# PumpMonitoring.net
KiCad netlist of a schematic drawn in EAGLE
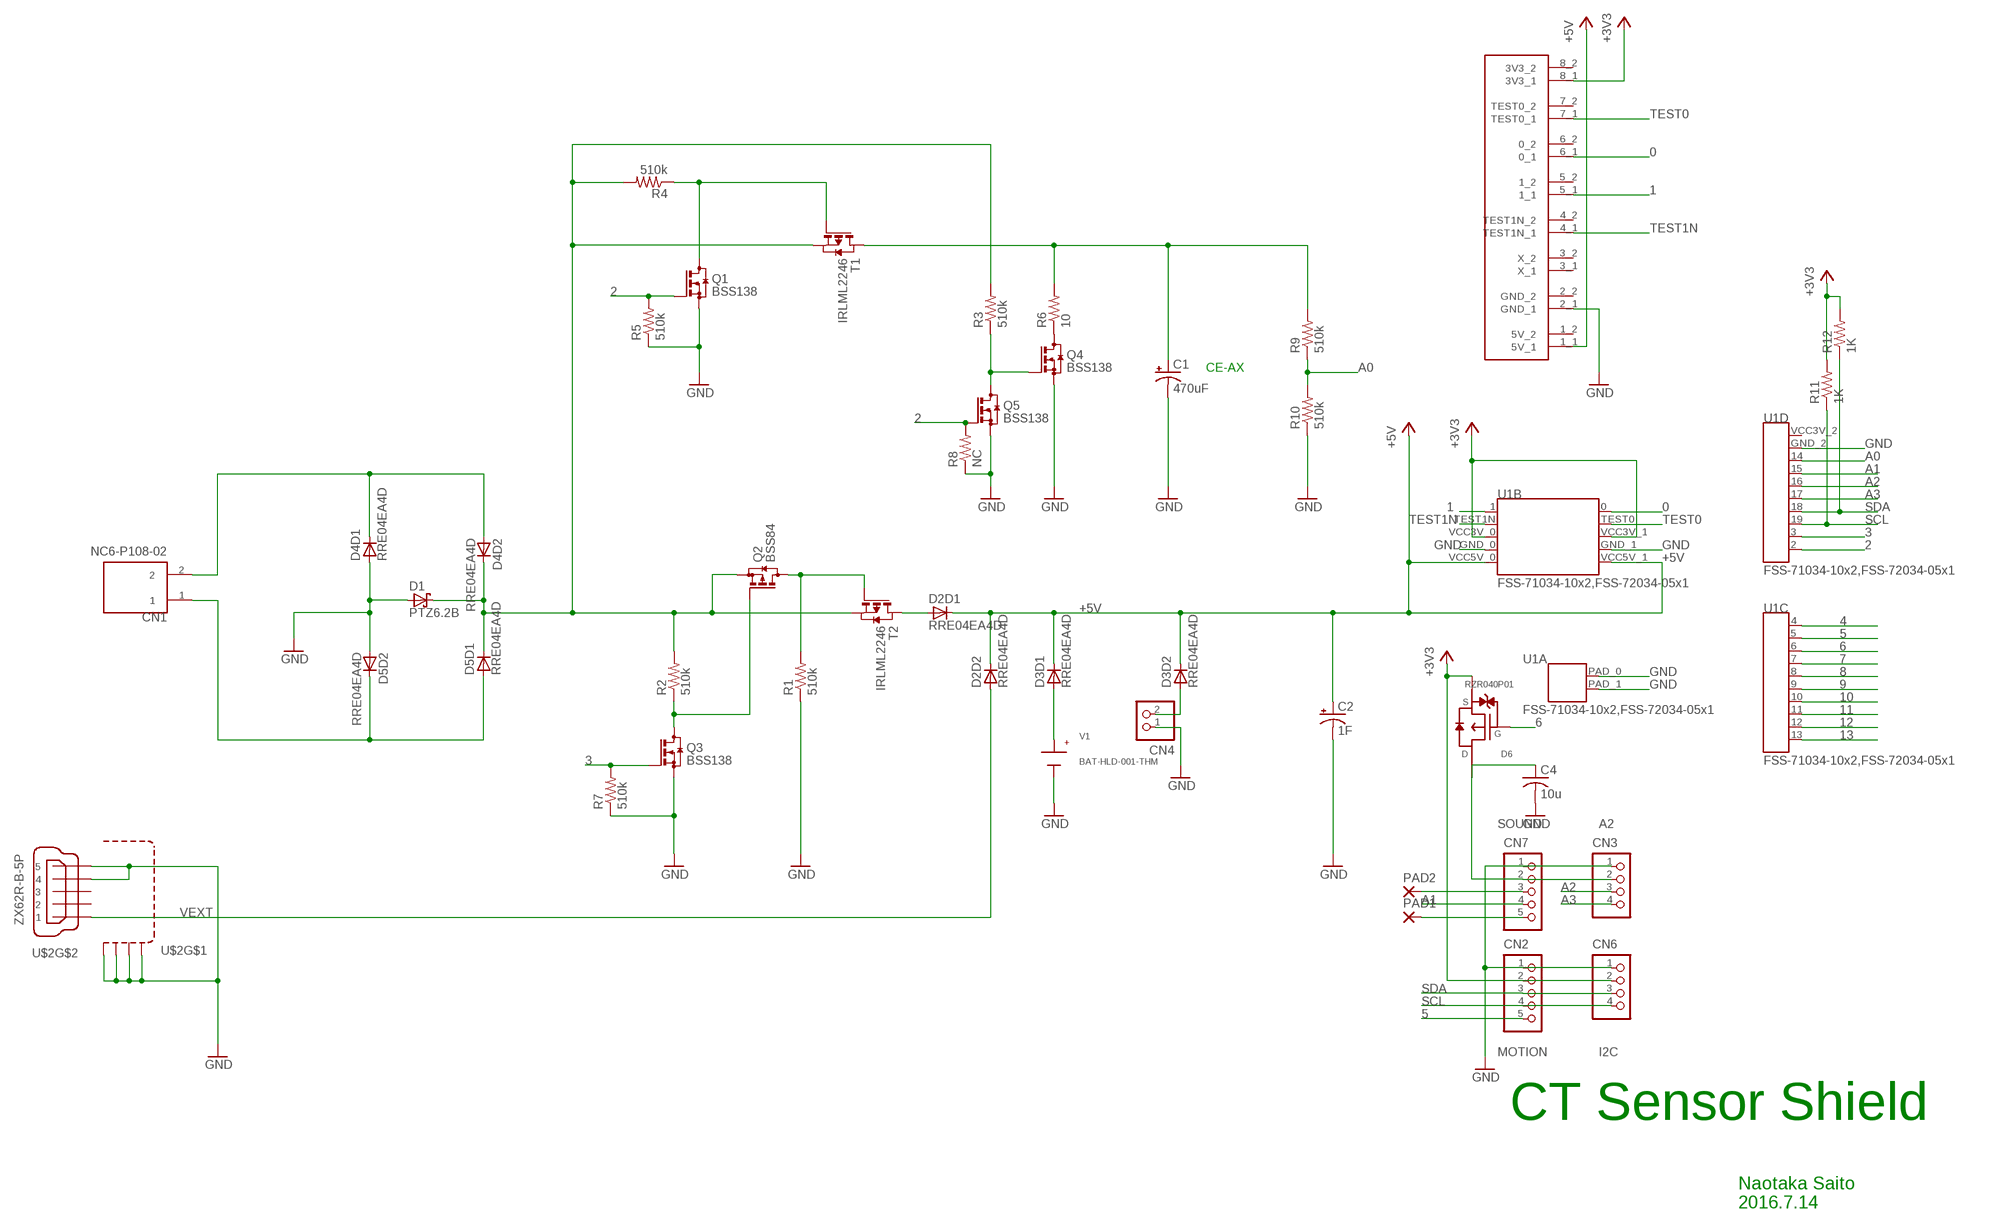
[diagram p0: schematic, sheet 1]

(export (version "E")
  (design (tool "Eeschema 10.0.6"))
  (components
    (comp (ref "C1")
      (value "470uF")
      (footprint "eagle-import:E5-10,5")
      (libsource (lib "eagle-import") (part "CPOL-USE5-10.5"))
    )
    (comp (ref "C2")
      (value "1F")
      (footprint "eagle-import:E5-20")
      (libsource (lib "eagle-import") (part "CPOL-USE5-20"))
    )
    (comp (ref "C4")
      (value "10u")
      (footprint "eagle-import:C1206")
      (libsource (lib "eagle-import") (part "C-USC1206"))
    )
    (comp (ref "CN1")
      (value "NC6-P108-02")
      (footprint "eagle-import:2PIN")
      (libsource (lib "eagle-import") (part "TE-NC6-P108-02"))
    )
    (comp (ref "CN2")
      (value "B5B-PH-K-S")
      (footprint "eagle-import:B5B-PH-K-S")
      (libsource (lib "eagle-import") (part "B5B-PH-K-S"))
    )
    (comp (ref "CN3")
      (value "B4B-PH-K-S")
      (footprint "eagle-import:B4B-PH-K-S")
      (libsource (lib "eagle-import") (part "B4B-PH-K-S"))
    )
    (comp (ref "CN4")
      (value "B2B-PH-K-S")
      (footprint "eagle-import:B2B-PH-K-S")
      (libsource (lib "eagle-import") (part "B2B-PH-K-S"))
    )
    (comp (ref "CN6")
      (value "B4B-PH-K-S")
      (footprint "eagle-import:B4B-PH-K-S")
      (libsource (lib "eagle-import") (part "B4B-PH-K-S"))
    )
    (comp (ref "CN7")
      (value "B5B-PH-K-S")
      (footprint "eagle-import:B5B-PH-K-S")
      (libsource (lib "eagle-import") (part "B5B-PH-K-S"))
    )
    (comp (ref "D1")
      (value "PTZ6.2B")
      (footprint "eagle-import:DO214AC")
      (libsource (lib "eagle-import") (part "PTZXXB"))
    )
    (comp (ref "D2")
      (value "RRE04EA4D")
      (footprint "eagle-import:TSMD5")
      (libsource (lib "eagle-import") (part "RRE04EA4D"))
    )
    (comp (ref "D3")
      (value "RRE04EA4D")
      (footprint "eagle-import:TSMD5")
      (libsource (lib "eagle-import") (part "RRE04EA4D"))
    )
    (comp (ref "D4")
      (value "RRE04EA4D")
      (footprint "eagle-import:TSMD5")
      (libsource (lib "eagle-import") (part "RRE04EA4D"))
    )
    (comp (ref "D5")
      (value "RRE04EA4D")
      (footprint "eagle-import:TSMD5")
      (libsource (lib "eagle-import") (part "RRE04EA4D"))
    )
    (comp (ref "D6")
      (value "RZR040P01")
      (footprint "eagle-import:TSMT3")
      (libsource (lib "eagle-import") (part "RZR040P01"))
    )
    (comp (ref "PAD1")
      (value "1,6/0,9")
      (footprint "eagle-import:1,6_0,9")
      (libsource (lib "eagle-import") (part "1,6/0,9"))
    )
    (comp (ref "PAD2")
      (value "1,6/0,9")
      (footprint "eagle-import:1,6_0,9")
      (libsource (lib "eagle-import") (part "1,6/0,9"))
    )
    (comp (ref "Q1")
      (value "BSS138")
      (footprint "eagle-import:SOT23")
      (libsource (lib "eagle-import") (part "BSS123"))
    )
    (comp (ref "Q2")
      (value "BSS84")
      (footprint "eagle-import:SOT23")
      (libsource (lib "eagle-import") (part "BSS84"))
    )
    (comp (ref "Q3")
      (value "BSS138")
      (footprint "eagle-import:SOT23")
      (libsource (lib "eagle-import") (part "BSS123"))
    )
    (comp (ref "Q4")
      (value "BSS138")
      (footprint "eagle-import:SOT23")
      (libsource (lib "eagle-import") (part "BSS123"))
    )
    (comp (ref "Q5")
      (value "BSS138")
      (footprint "eagle-import:SOT23")
      (libsource (lib "eagle-import") (part "BSS123"))
    )
    (comp (ref "R1")
      (value "510k")
      (footprint "eagle-import:R0603")
      (libsource (lib "eagle-import") (part "R-US_R0603"))
    )
    (comp (ref "R2")
      (value "510k")
      (footprint "eagle-import:R0603")
      (libsource (lib "eagle-import") (part "R-US_R0603"))
    )
    (comp (ref "R3")
      (value "510k")
      (footprint "eagle-import:R0603")
      (libsource (lib "eagle-import") (part "R-US_R0603"))
    )
    (comp (ref "R4")
      (value "510k")
      (footprint "eagle-import:R0603")
      (libsource (lib "eagle-import") (part "R-US_R0603"))
    )
    (comp (ref "R5")
      (value "510k")
      (footprint "eagle-import:R0603")
      (libsource (lib "eagle-import") (part "R-US_R0603"))
    )
    (comp (ref "R6")
      (value "10")
      (footprint "eagle-import:EZP")
      (libsource (lib "eagle-import") (part "MCR18"))
    )
    (comp (ref "R7")
      (value "510k")
      (footprint "eagle-import:R0603")
      (libsource (lib "eagle-import") (part "R-US_R0603"))
    )
    (comp (ref "R8")
      (value "NC")
      (footprint "eagle-import:R0603")
      (libsource (lib "eagle-import") (part "R-US_R0603"))
    )
    (comp (ref "R9")
      (value "510k")
      (footprint "eagle-import:R0603")
      (libsource (lib "eagle-import") (part "R-US_R0603"))
    )
    (comp (ref "R10")
      (value "510k")
      (footprint "eagle-import:R0603")
      (libsource (lib "eagle-import") (part "R-US_R0603"))
    )
    (comp (ref "R11")
      (value "1K")
      (footprint "eagle-import:R0603")
      (libsource (lib "eagle-import") (part "R-US_R0603"))
    )
    (comp (ref "R12")
      (value "1K")
      (footprint "eagle-import:R0603")
      (libsource (lib "eagle-import") (part "R-US_R0603"))
    )
    (comp (ref "T1")
      (value "IRLML2246")
      (footprint "eagle-import:SOT-23")
      (libsource (lib "eagle-import") (part "PMOSSOT23"))
    )
    (comp (ref "T2")
      (value "IRLML2246")
      (footprint "eagle-import:SOT-23")
      (libsource (lib "eagle-import") (part "PMOSSOT23"))
    )
    (comp (ref "U$1")
      (value "XB-1-X")
      (footprint "eagle-import:XB-1-X")
      (libsource (lib "eagle-import") (part "XB-1-X"))
    )
    (comp (ref "U$2")
      (value "ZX62R-B-5P")
      (footprint "eagle-import:ZX62R-B-5P")
      (libsource (lib "eagle-import") (part "MICRO-USB-SHIELD-ZX62R-B-5P"))
    )
    (comp (ref "U1")
      (value "FSS-71034-10x2,FSS-72034-05x1")
      (footprint "eagle-import:LAZURITE920J")
      (libsource (lib "eagle-import") (part "LAZURITE920JLAZURITE920J"))
    )
    (comp (ref "V1")
      (value "BAT-HLD-001-THM")
      (footprint "eagle-import:CR2032")
      (libsource (lib "eagle-import") (part "BAT-HLD-001-THM"))
    )
  )
  (nets
    (net (code "1") (name "+3V3") (class "Default")
      (node (ref "CN2") (pin "2") (pinfunction "2_2") (pintype "passive"))
      (node (ref "CN6") (pin "2") (pinfunction "2_2") (pintype "passive"))
      (node (ref "D6") (pin "2") (pinfunction "S_2") (pintype "bidirectional"))
      (node (ref "R11") (pin "2") (pinfunction "2_2") (pintype "passive"))
      (node (ref "R12") (pin "2") (pinfunction "2_2") (pintype "passive"))
      (node (ref "U$1") (pin "8_1") (pinfunction "3V3_1_8_1") (pintype "bidirectional"))
      (node (ref "U1") (pin "VCC3V_0") (pinfunction "VCC3V_0_VCC3V_0") (pintype "passive"))
      (node (ref "U1") (pin "VCC3V_1") (pinfunction "VCC3V_1_VCC3V_1") (pintype "passive"))
    )
    (net (code "2") (name "+5V") (class "Default")
      (node (ref "C2") (pin "+") (pinfunction "+_+") (pintype "passive"))
      (node (ref "D2") (pin "4") (pinfunction "C_4") (pintype "passive"))
      (node (ref "D2") (pin "5") (pinfunction "C_5") (pintype "passive"))
      (node (ref "D3") (pin "4") (pinfunction "C_4") (pintype "passive"))
      (node (ref "D3") (pin "5") (pinfunction "C_5") (pintype "passive"))
      (node (ref "U$1") (pin "1_1") (pinfunction "5V_1_1_1") (pintype "bidirectional"))
      (node (ref "U1") (pin "VCC5V_0") (pinfunction "VCC5V_0_VCC5V_0") (pintype "passive"))
      (node (ref "U1") (pin "VCC5V_1") (pinfunction "VCC5V_1_VCC5V_1") (pintype "passive"))
    )
    (net (code "3") (name "/0") (class "Default")
      (node (ref "U$1") (pin "6_1") (pinfunction "0_1_6_1") (pintype "bidirectional"))
      (node (ref "U1") (pin "0") (pinfunction "0_0") (pintype "passive"))
    )
    (net (code "4") (name "/1") (class "Default")
      (node (ref "U$1") (pin "5_1") (pinfunction "1_1_5_1") (pintype "bidirectional"))
      (node (ref "U1") (pin "1") (pinfunction "1_1") (pintype "passive"))
    )
    (net (code "5") (name "/2") (class "Default")
      (node (ref "Q1") (pin "1") (pinfunction "G_1") (pintype "passive"))
      (node (ref "Q5") (pin "1") (pinfunction "G_1") (pintype "passive"))
      (node (ref "R5") (pin "2") (pinfunction "2_2") (pintype "passive"))
      (node (ref "R8") (pin "2") (pinfunction "2_2") (pintype "passive"))
      (node (ref "U1") (pin "2") (pinfunction "2_2") (pintype "passive"))
    )
    (net (code "6") (name "/3") (class "Default")
      (node (ref "Q3") (pin "1") (pinfunction "G_1") (pintype "passive"))
      (node (ref "R7") (pin "2") (pinfunction "2_2") (pintype "passive"))
      (node (ref "U1") (pin "3") (pinfunction "3_3") (pintype "passive"))
    )
    (net (code "7") (name "/4") (class "Default")
      (node (ref "U1") (pin "4") (pinfunction "4_4") (pintype "passive"))
    )
    (net (code "8") (name "/5") (class "Default")
      (node (ref "CN2") (pin "5") (pinfunction "5_5") (pintype "passive"))
      (node (ref "U1") (pin "5") (pinfunction "5_5") (pintype "passive"))
    )
    (net (code "9") (name "/6") (class "Default")
      (node (ref "D6") (pin "1") (pinfunction "G_1") (pintype "bidirectional"))
      (node (ref "U1") (pin "6") (pinfunction "6_6") (pintype "passive"))
    )
    (net (code "10") (name "/7") (class "Default")
      (node (ref "U1") (pin "7") (pinfunction "7_7") (pintype "passive"))
    )
    (net (code "11") (name "/8") (class "Default")
      (node (ref "U1") (pin "8") (pinfunction "8_8") (pintype "passive"))
    )
    (net (code "12") (name "/9") (class "Default")
      (node (ref "U1") (pin "9") (pinfunction "9_9") (pintype "passive"))
    )
    (net (code "13") (name "/10") (class "Default")
      (node (ref "U1") (pin "10") (pinfunction "10_10") (pintype "passive"))
    )
    (net (code "14") (name "/11") (class "Default")
      (node (ref "U1") (pin "11") (pinfunction "11_11") (pintype "passive"))
    )
    (net (code "15") (name "/12") (class "Default")
      (node (ref "U1") (pin "12") (pinfunction "12_12") (pintype "passive"))
    )
    (net (code "16") (name "/13") (class "Default")
      (node (ref "U1") (pin "13") (pinfunction "13_13") (pintype "passive"))
    )
    (net (code "17") (name "/A0") (class "Default")
      (node (ref "R10") (pin "2") (pinfunction "2_2") (pintype "passive"))
      (node (ref "R9") (pin "1") (pinfunction "1_1") (pintype "passive"))
      (node (ref "U1") (pin "14") (pinfunction "14_14") (pintype "passive"))
    )
    (net (code "18") (name "/A1") (class "Default")
      (node (ref "CN7") (pin "4") (pinfunction "4_4") (pintype "passive"))
      (node (ref "U1") (pin "15") (pinfunction "15_15") (pintype "passive"))
    )
    (net (code "19") (name "/A2") (class "Default")
      (node (ref "CN3") (pin "3") (pinfunction "3_3") (pintype "passive"))
      (node (ref "U1") (pin "16") (pinfunction "16_16") (pintype "passive"))
    )
    (net (code "20") (name "/A3") (class "Default")
      (node (ref "CN3") (pin "4") (pinfunction "4_4") (pintype "passive"))
      (node (ref "U1") (pin "17") (pinfunction "17_17") (pintype "passive"))
    )
    (net (code "21") (name "/SCL") (class "Default")
      (node (ref "CN2") (pin "4") (pinfunction "4_4") (pintype "passive"))
      (node (ref "CN6") (pin "4") (pinfunction "4_4") (pintype "passive"))
      (node (ref "R11") (pin "1") (pinfunction "1_1") (pintype "passive"))
      (node (ref "U1") (pin "19") (pinfunction "19_19") (pintype "passive"))
    )
    (net (code "22") (name "/SDA") (class "Default")
      (node (ref "CN2") (pin "3") (pinfunction "3_3") (pintype "passive"))
      (node (ref "CN6") (pin "3") (pinfunction "3_3") (pintype "passive"))
      (node (ref "R12") (pin "1") (pinfunction "1_1") (pintype "passive"))
      (node (ref "U1") (pin "18") (pinfunction "18_18") (pintype "passive"))
    )
    (net (code "23") (name "/TEST0") (class "Default")
      (node (ref "U$1") (pin "7_1") (pinfunction "TEST0_1_7_1") (pintype "bidirectional"))
      (node (ref "U1") (pin "TEST0") (pinfunction "TEST0_TEST0") (pintype "passive"))
    )
    (net (code "24") (name "/TEST1N") (class "Default")
      (node (ref "U$1") (pin "4_1") (pinfunction "TEST1N_1_4_1") (pintype "bidirectional"))
      (node (ref "U1") (pin "TEST1N") (pinfunction "TEST1N_TEST1N") (pintype "passive"))
    )
    (net (code "25") (name "/VEXT") (class "Default")
      (node (ref "D2") (pin "3") (pinfunction "A_3") (pintype "passive"))
      (node (ref "U$2") (pin "1") (pinfunction "1_1") (pintype "input"))
    )
    (net (code "26") (name "GND") (class "Default")
      (node (ref "C1") (pin "-") (pinfunction "-_-") (pintype "passive"))
      (node (ref "C2") (pin "-") (pinfunction "-_-") (pintype "passive"))
      (node (ref "C4") (pin "2") (pinfunction "2_2") (pintype "passive"))
      (node (ref "CN2") (pin "1") (pinfunction "1_1") (pintype "passive"))
      (node (ref "CN3") (pin "1") (pinfunction "1_1") (pintype "passive"))
      (node (ref "CN4") (pin "1") (pinfunction "1_1") (pintype "passive"))
      (node (ref "CN6") (pin "1") (pinfunction "1_1") (pintype "passive"))
      (node (ref "CN7") (pin "1") (pinfunction "1_1") (pintype "passive"))
      (node (ref "D1") (pin "A") (pinfunction "A_A") (pintype "passive"))
      (node (ref "D4") (pin "1") (pinfunction "A_1") (pintype "passive"))
      (node (ref "D5") (pin "3") (pinfunction "A_3") (pintype "passive"))
      (node (ref "Q1") (pin "2") (pinfunction "S_2") (pintype "passive"))
      (node (ref "Q3") (pin "2") (pinfunction "S_2") (pintype "passive"))
      (node (ref "Q4") (pin "2") (pinfunction "S_2") (pintype "passive"))
      (node (ref "Q5") (pin "2") (pinfunction "S_2") (pintype "passive"))
      (node (ref "R1") (pin "1") (pinfunction "1_1") (pintype "passive"))
      (node (ref "R10") (pin "1") (pinfunction "1_1") (pintype "passive"))
      (node (ref "R5") (pin "1") (pinfunction "1_1") (pintype "passive"))
      (node (ref "R7") (pin "1") (pinfunction "1_1") (pintype "passive"))
      (node (ref "R8") (pin "1") (pinfunction "1_1") (pintype "passive"))
      (node (ref "U$1") (pin "2_1") (pinfunction "GND_1_2_1") (pintype "bidirectional"))
      (node (ref "U$2") (pin "4") (pinfunction "4_4") (pintype "input"))
      (node (ref "U$2") (pin "5") (pinfunction "5_5") (pintype "input"))
      (node (ref "U$2") (pin "M1") (pinfunction "S1_M1") (pintype "passive"))
      (node (ref "U$2") (pin "M2") (pinfunction "S2_M2") (pintype "passive"))
      (node (ref "U$2") (pin "M3") (pinfunction "S3_M3") (pintype "passive"))
      (node (ref "U$2") (pin "M4") (pinfunction "S4_M4") (pintype "passive"))
      (node (ref "U1") (pin "GND_0") (pinfunction "GND_0_GND_0") (pintype "passive"))
      (node (ref "U1") (pin "GND_1") (pinfunction "GND_1_GND_1") (pintype "passive"))
      (node (ref "U1") (pin "GND_2") (pinfunction "GND_2_GND_2") (pintype "passive"))
      (node (ref "U1") (pin "PAD_0") (pinfunction "PAD_0_PAD_0") (pintype "passive"))
      (node (ref "U1") (pin "PAD_1") (pinfunction "PAD_1_PAD_1") (pintype "passive"))
      (node (ref "V1") (pin "GND") (pinfunction "GND_GND") (pintype "power_in"))
    )
    (net (code "27") (name "Net-(D2A-A)") (class "Default")
      (node (ref "D2") (pin "1") (pinfunction "A_1") (pintype "passive"))
      (node (ref "T2") (pin "1") (pinfunction "D_1") (pintype "passive"))
    )
    (net (code "28") (name "Net-(D3A-A)") (class "Default")
      (node (ref "D3") (pin "1") (pinfunction "A_1") (pintype "passive"))
      (node (ref "V1") (pin "VDD1") (pinfunction "VDD_VDD1") (pintype "power_in"))
      (node (ref "V1") (pin "VDD2") (pinfunction "VDD_VDD2") (pintype "power_in"))
      (node (ref "V1") (pin "VDD3") (pinfunction "VDD_VDD3") (pintype "power_in"))
      (node (ref "V1") (pin "VDD4") (pinfunction "VDD_VDD4") (pintype "power_in"))
    )
    (net (code "29") (name "Net-(D3B-A)") (class "Default")
      (node (ref "CN4") (pin "2") (pinfunction "2_2") (pintype "passive"))
      (node (ref "D3") (pin "3") (pinfunction "A_3") (pintype "passive"))
    )
    (net (code "30") (name "Net-(D4A-C)") (class "Default")
      (node (ref "CN1") (pin "2") (pinfunction "2_2") (pintype "passive"))
      (node (ref "D4") (pin "3") (pinfunction "A_3") (pintype "passive"))
      (node (ref "D4") (pin "5") (pinfunction "C_5") (pintype "passive"))
    )
    (net (code "31") (name "Net-(D4B-C)") (class "Default")
      (node (ref "D1") (pin "C") (pinfunction "C_C") (pintype "passive"))
      (node (ref "D4") (pin "4") (pinfunction "C_4") (pintype "passive"))
      (node (ref "D5") (pin "5") (pinfunction "C_5") (pintype "passive"))
      (node (ref "Q2") (pin "2") (pinfunction "S_2") (pintype "passive"))
      (node (ref "R2") (pin "2") (pinfunction "2_2") (pintype "passive"))
      (node (ref "R3") (pin "2") (pinfunction "2_2") (pintype "passive"))
      (node (ref "R4") (pin "2") (pinfunction "2_2") (pintype "passive"))
      (node (ref "T1") (pin "2") (pinfunction "S_2") (pintype "passive"))
      (node (ref "T2") (pin "2") (pinfunction "S_2") (pintype "passive"))
    )
    (net (code "32") (name "Net-(D5A-A)") (class "Default")
      (node (ref "CN1") (pin "1") (pinfunction "1_1") (pintype "passive"))
      (node (ref "D5") (pin "1") (pinfunction "A_1") (pintype "passive"))
      (node (ref "D5") (pin "4") (pinfunction "C_4") (pintype "passive"))
    )
    (net (code "33") (name "Net-(D6-D)") (class "Default")
      (node (ref "C4") (pin "1") (pinfunction "1_1") (pintype "passive"))
      (node (ref "CN3") (pin "2") (pinfunction "2_2") (pintype "passive"))
      (node (ref "CN7") (pin "2") (pinfunction "2_2") (pintype "passive"))
      (node (ref "D6") (pin "3") (pinfunction "D_3") (pintype "bidirectional"))
    )
    (net (code "34") (name "Net-(PAD1-P)") (class "Default")
      (node (ref "CN7") (pin "5") (pinfunction "5_5") (pintype "passive"))
      (node (ref "PAD1") (pin "1") (pinfunction "P_1") (pintype "passive"))
    )
    (net (code "35") (name "Net-(PAD2-P)") (class "Default")
      (node (ref "CN7") (pin "3") (pinfunction "3_3") (pintype "passive"))
      (node (ref "PAD2") (pin "1") (pinfunction "P_1") (pintype "passive"))
    )
    (net (code "36") (name "Net-(Q1-D)") (class "Default")
      (node (ref "Q1") (pin "3") (pinfunction "D_3") (pintype "passive"))
      (node (ref "R4") (pin "1") (pinfunction "1_1") (pintype "passive"))
      (node (ref "T1") (pin "3") (pinfunction "G_3") (pintype "passive"))
    )
    (net (code "37") (name "Net-(Q2-D)") (class "Default")
      (node (ref "Q2") (pin "3") (pinfunction "D_3") (pintype "passive"))
      (node (ref "R1") (pin "2") (pinfunction "2_2") (pintype "passive"))
      (node (ref "T2") (pin "3") (pinfunction "G_3") (pintype "passive"))
    )
    (net (code "38") (name "Net-(Q2-G)") (class "Default")
      (node (ref "Q2") (pin "1") (pinfunction "G_1") (pintype "passive"))
      (node (ref "Q3") (pin "3") (pinfunction "D_3") (pintype "passive"))
      (node (ref "R2") (pin "1") (pinfunction "1_1") (pintype "passive"))
    )
    (net (code "39") (name "Net-(Q4-D)") (class "Default")
      (node (ref "Q4") (pin "3") (pinfunction "D_3") (pintype "passive"))
      (node (ref "R6") (pin "1") (pinfunction "1_1") (pintype "passive"))
    )
    (net (code "40") (name "Net-(Q4-G)") (class "Default")
      (node (ref "Q4") (pin "1") (pinfunction "G_1") (pintype "passive"))
      (node (ref "Q5") (pin "3") (pinfunction "D_3") (pintype "passive"))
      (node (ref "R3") (pin "1") (pinfunction "1_1") (pintype "passive"))
    )
    (net (code "41") (name "Net-(T1-D)") (class "Default")
      (node (ref "C1") (pin "+") (pinfunction "+_+") (pintype "passive"))
      (node (ref "R6") (pin "2") (pinfunction "2_2") (pintype "passive"))
      (node (ref "R9") (pin "2") (pinfunction "2_2") (pintype "passive"))
      (node (ref "T1") (pin "1") (pinfunction "D_1") (pintype "passive"))
    )
    (net (code "42") (name "unconnected-(U$1-0_2-Pad6_2)") (class "Default")
      (node (ref "U$1") (pin "6_2") (pinfunction "0_2_6_2") (pintype "bidirectional"))
    )
    (net (code "43") (name "unconnected-(U$1-1_2-Pad5_2)") (class "Default")
      (node (ref "U$1") (pin "5_2") (pinfunction "1_2_5_2") (pintype "bidirectional"))
    )
    (net (code "44") (name "unconnected-(U$1-3V3_2-Pad8_2)") (class "Default")
      (node (ref "U$1") (pin "8_2") (pinfunction "3V3_2_8_2") (pintype "bidirectional"))
    )
    (net (code "45") (name "unconnected-(U$1-5V_2-Pad1_2)") (class "Default")
      (node (ref "U$1") (pin "1_2") (pinfunction "5V_2_1_2") (pintype "bidirectional"))
    )
    (net (code "46") (name "unconnected-(U$1-GND_2-Pad2_2)") (class "Default")
      (node (ref "U$1") (pin "2_2") (pinfunction "GND_2_2_2") (pintype "bidirectional"))
    )
    (net (code "47") (name "unconnected-(U$1-TEST0_2-Pad7_2)") (class "Default")
      (node (ref "U$1") (pin "7_2") (pinfunction "TEST0_2_7_2") (pintype "bidirectional"))
    )
    (net (code "48") (name "unconnected-(U$1-TEST1N_2-Pad4_2)") (class "Default")
      (node (ref "U$1") (pin "4_2") (pinfunction "TEST1N_2_4_2") (pintype "bidirectional"))
    )
    (net (code "49") (name "unconnected-(U$1-X_1-Pad3_1)") (class "Default")
      (node (ref "U$1") (pin "3_1") (pinfunction "X_1_3_1") (pintype "bidirectional"))
    )
    (net (code "50") (name "unconnected-(U$1-X_2-Pad3_2)") (class "Default")
      (node (ref "U$1") (pin "3_2") (pinfunction "X_2_3_2") (pintype "bidirectional"))
    )
    (net (code "51") (name "unconnected-(U$2-Pad2)") (class "Default")
      (node (ref "U$2") (pin "2") (pinfunction "2_2") (pintype "input"))
    )
    (net (code "52") (name "unconnected-(U$2-Pad3)") (class "Default")
      (node (ref "U$2") (pin "3") (pinfunction "3_3") (pintype "input"))
    )
    (net (code "53") (name "unconnected-(U1-PadVCC3V_2)") (class "Default")
      (node (ref "U1") (pin "VCC3V_2") (pinfunction "VCC3V_2_VCC3V_2") (pintype "passive"))
    )
  )
)
